# DRV8432.net
KiCad netlist of a schematic drawn in Altium Designer
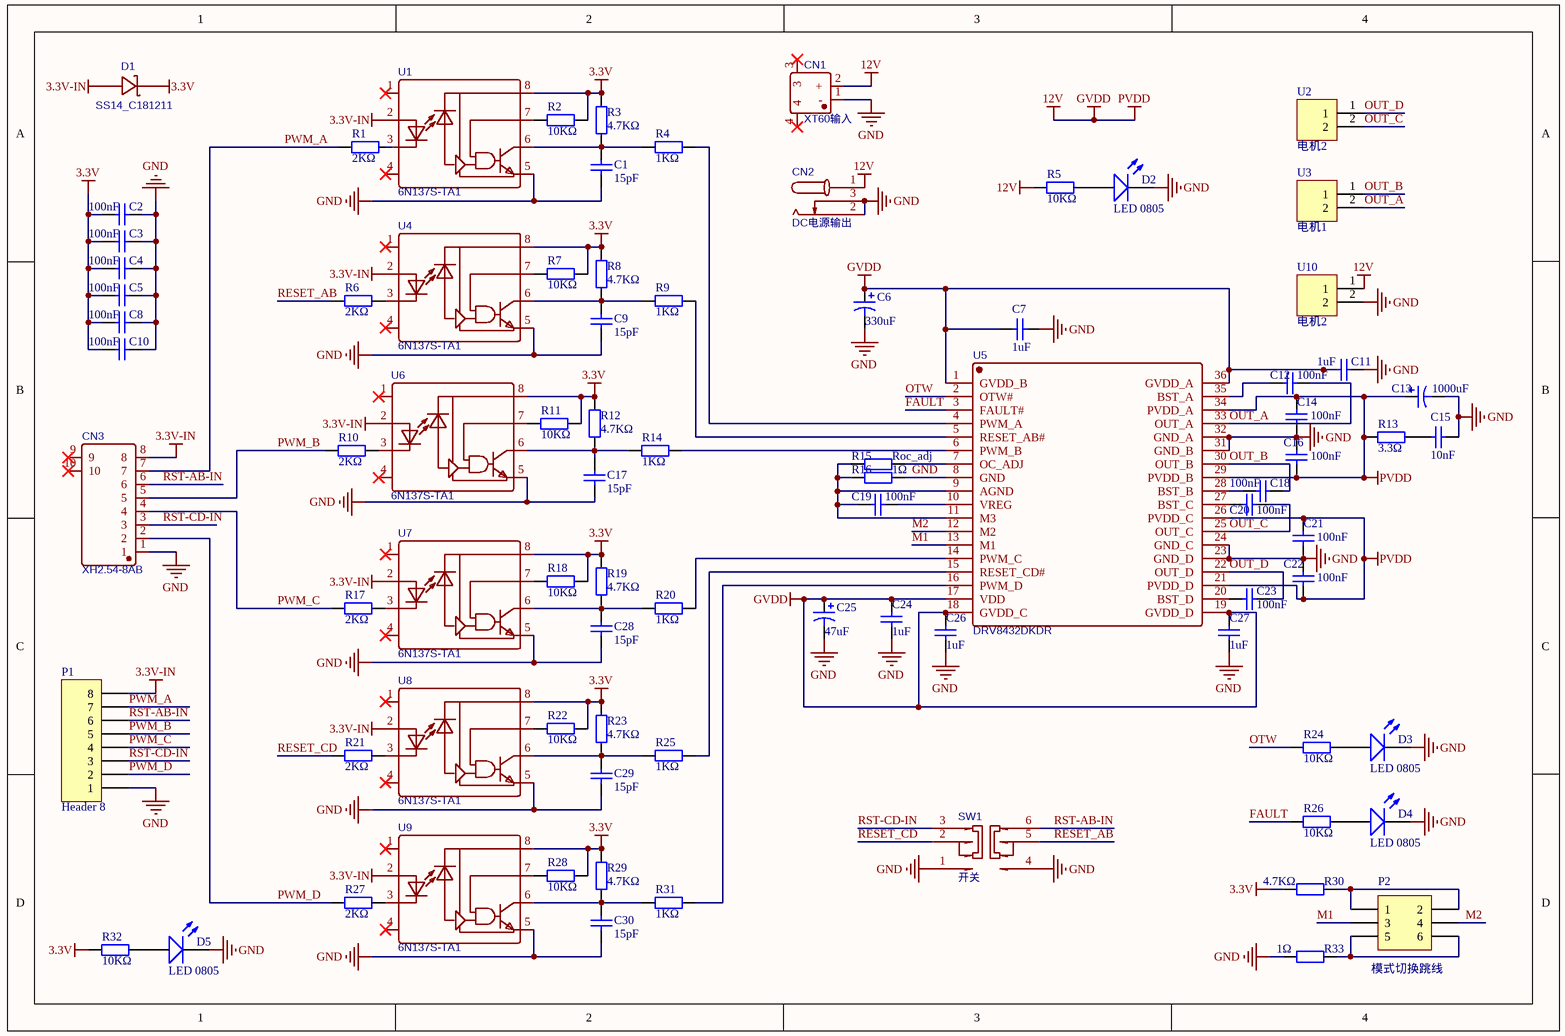
[diagram p0: DRV8432有刷直流电机驱动.SchDoc]

(export (version "E")
  (design (tool "Eeschema 10.0.6"))
  (components
    (comp (ref "C1")
      (value "15pF")
      (footprint "0805_C")
      (description "贴片电容")
      (libsource (lib "Miscellaneous Devices LC") (part "0805 15pF (150) 5% 50V"))
    )
    (comp (ref "C2")
      (value "100nF")
      (footprint "0805_C")
      (description "贴片电容")
      (libsource (lib "Miscellaneous Devices LC") (part "0805 100nF(104) 10% 50V"))
    )
    (comp (ref "C3")
      (value "100nF")
      (footprint "0805_C")
      (description "贴片电容")
      (libsource (lib "Miscellaneous Devices LC") (part "0805 100nF(104) 10% 50V"))
    )
    (comp (ref "C4")
      (value "100nF")
      (footprint "0805_C")
      (description "贴片电容")
      (libsource (lib "Miscellaneous Devices LC") (part "0805 100nF(104) 10% 50V"))
    )
    (comp (ref "C5")
      (value "100nF")
      (footprint "0805_C")
      (description "贴片电容")
      (libsource (lib "Miscellaneous Devices LC") (part "0805 100nF(104) 10% 50V"))
    )
    (comp (ref "C6")
      (value "330uF")
      (footprint "CAP-TH_BD8.0-P3.50-D0.6-FD")
      (description "Polarized Capacitor (Radial)")
      (fields (field (name "Comment") "Cap Pol1") (field (name "PUBLISHER") "Altium Limited"))
      (libsource (lib "Miscellaneous Devices") (part "Cap Pol1"))
    )
    (comp (ref "C7")
      (value "1uF")
      (footprint "0805_C")
      (description "贴片电容")
      (libsource (lib "Miscellaneous Devices LC") (part "0805 1uF (105) 10% 50V"))
    )
    (comp (ref "C8")
      (value "100nF")
      (footprint "0805_C")
      (description "贴片电容")
      (libsource (lib "Miscellaneous Devices LC") (part "0805 100nF(104) 10% 50V"))
    )
    (comp (ref "C9")
      (value "15pF")
      (footprint "0805_C")
      (description "贴片电容")
      (libsource (lib "Miscellaneous Devices LC") (part "0805 15pF (150) 5% 50V"))
    )
    (comp (ref "C10")
      (value "100nF")
      (footprint "0805_C")
      (description "贴片电容")
      (libsource (lib "Miscellaneous Devices LC") (part "0805 100nF(104) 10% 50V"))
    )
    (comp (ref "C11")
      (value "1uF")
      (footprint "0805_C")
      (description "贴片电容")
      (libsource (lib "Miscellaneous Devices LC") (part "0805 1uF (105) 10% 50V"))
    )
    (comp (ref "C12")
      (value "100nF")
      (footprint "0805_C")
      (description "贴片电容")
      (libsource (lib "Miscellaneous Devices LC") (part "0805 100nF(104) 10% 50V"))
    )
    (comp (ref "C13")
      (value "1000uF")
      (footprint "CAP-TH_BD25.0-P10.00-D2.3-FD")
      (description "Polarized Capacitor (Radial)")
      (fields (field (name "Comment") "Cap Pol1") (field (name "PUBLISHER") "Altium Limited"))
      (libsource (lib "Miscellaneous Devices") (part "Cap Pol1"))
    )
    (comp (ref "C14")
      (value "100nF")
      (footprint "0805_C")
      (description "贴片电容")
      (libsource (lib "Miscellaneous Devices LC") (part "0805 100nF(104) 10% 50V"))
    )
    (comp (ref "C15")
      (value "10nF")
      (footprint "0805_C")
      (description "贴片电容")
      (libsource (lib "Miscellaneous Devices LC") (part "0805 10nF (103) 10% 50V"))
    )
    (comp (ref "C16")
      (value "100nF")
      (footprint "0805_C")
      (description "贴片电容")
      (libsource (lib "Miscellaneous Devices LC") (part "0805 100nF(104) 10% 50V"))
    )
    (comp (ref "C17")
      (value "15pF")
      (footprint "0805_C")
      (description "贴片电容")
      (libsource (lib "Miscellaneous Devices LC") (part "0805 15pF (150) 5% 50V"))
    )
    (comp (ref "C18")
      (value "100nF")
      (footprint "0805_C")
      (description "贴片电容")
      (libsource (lib "Miscellaneous Devices LC") (part "0805 100nF(104) 10% 50V"))
    )
    (comp (ref "C19")
      (value "100nF")
      (footprint "0805_C")
      (description "贴片电容")
      (libsource (lib "Miscellaneous Devices LC") (part "0805 100nF(104) 10% 50V"))
    )
    (comp (ref "C20")
      (value "100nF")
      (footprint "0805_C")
      (description "贴片电容")
      (libsource (lib "Miscellaneous Devices LC") (part "0805 100nF(104) 10% 50V"))
    )
    (comp (ref "C21")
      (value "100nF")
      (footprint "0805_C")
      (description "贴片电容")
      (libsource (lib "Miscellaneous Devices LC") (part "0805 100nF(104) 10% 50V"))
    )
    (comp (ref "C22")
      (value "100nF")
      (footprint "0805_C")
      (description "贴片电容")
      (libsource (lib "Miscellaneous Devices LC") (part "0805 100nF(104) 10% 50V"))
    )
    (comp (ref "C23")
      (value "100nF")
      (footprint "0805_C")
      (description "贴片电容")
      (libsource (lib "Miscellaneous Devices LC") (part "0805 100nF(104) 10% 50V"))
    )
    (comp (ref "C24")
      (value "1uF")
      (footprint "0805_C")
      (description "贴片电容")
      (libsource (lib "Miscellaneous Devices LC") (part "0805 1uF (105) 10% 50V"))
    )
    (comp (ref "C25")
      (value "47uF")
      (footprint "CAP-TH_BD5.0-P2.00-D0.8-FD")
      (description "Polarized Capacitor (Radial)")
      (fields (field (name "Comment") "Cap Pol1") (field (name "PUBLISHER") "Altium Limited"))
      (libsource (lib "Miscellaneous Devices") (part "Cap Pol1"))
    )
    (comp (ref "C26")
      (value "1uF")
      (footprint "0805_C")
      (description "贴片电容")
      (libsource (lib "Miscellaneous Devices LC") (part "0805 1uF (105) 10% 50V"))
    )
    (comp (ref "C27")
      (value "1uF")
      (footprint "0805_C")
      (description "贴片电容")
      (libsource (lib "Miscellaneous Devices LC") (part "0805 1uF (105) 10% 50V"))
    )
    (comp (ref "C28")
      (value "15pF")
      (footprint "0805_C")
      (description "贴片电容")
      (libsource (lib "Miscellaneous Devices LC") (part "0805 15pF (150) 5% 50V"))
    )
    (comp (ref "C29")
      (value "15pF")
      (footprint "0805_C")
      (description "贴片电容")
      (libsource (lib "Miscellaneous Devices LC") (part "0805 15pF (150) 5% 50V"))
    )
    (comp (ref "C30")
      (value "15pF")
      (footprint "0805_C")
      (description "贴片电容")
      (libsource (lib "Miscellaneous Devices LC") (part "0805 15pF (150) 5% 50V"))
    )
    (comp (ref "CN1")
      (value "XT60输入")
      (footprint "XT60座子")
      (fields
        (field (name "BOM_SUPPLIER PART") "C98732")
        (field (name "BOM_MANUFACTURER PART") "XT60PW-M")
        (field (name "CONTRIBUTOR") "LCSC")
      )
      (libsource (lib "2021全地形") (part "XT60"))
    )
    (comp (ref "CN2")
      (value "DC电源输出")
      (footprint "DC接口5.5*2.1")
      (fields
        (field (name "BOM_MANUFACTURER PART") "DC-005-20A")
        (field (name "BOM_SUPPLIER PART") "C136744")
        (field (name "CONTRIBUTOR") "LCSC")
      )
      (libsource (lib "2021全地形") (part "DC接口2251"))
    )
    (comp (ref "CN3")
      (value "XH2.54-8AB")
      (footprint "CONN-SMD_8P-P2.54_XH2.54-8AB")
      (fields (field (name "BOM_SUPPLIER PART") "C146131") (field (name "CONTRIBUTOR") "LCSC"))
      (libsource (lib "2021全地形") (part "XH2.54-8AB"))
    )
    (comp (ref "D1")
      (value "SS14_C181211")
      (footprint "SMA_L4.4-W2.8-LS5.4-RD")
      (fields
        (field (name "BOM_MANUFACTURER PART") "SS14")
        (field (name "BOM_SUPPLIER PART") "C181211")
        (field (name "CONTRIBUTOR") "LCSC")
      )
      (libsource (lib "2021全地形") (part "SS14_C181211"))
    )
    (comp (ref "D2")
      (value "LED 0805")
      (footprint "0805_LED_S1")
      (description "发光二极管")
      (libsource (lib "Miscellaneous Devices LC") (part "0805 白灯"))
    )
    (comp (ref "D3")
      (value "LED 0805")
      (footprint "0805_LED_S1")
      (description "发光二极管")
      (libsource (lib "Miscellaneous Devices LC") (part "0805 白灯"))
    )
    (comp (ref "D4")
      (value "LED 0805")
      (footprint "0805_LED_S1")
      (description "发光二极管")
      (libsource (lib "Miscellaneous Devices LC") (part "0805 白灯"))
    )
    (comp (ref "D5")
      (value "LED 0805")
      (footprint "0805_LED_S1")
      (description "发光二极管")
      (libsource (lib "Miscellaneous Devices LC") (part "0805 白灯"))
    )
    (comp (ref "P1")
      (value "Header 8")
      (footprint "HDR1X8")
      (description "Header, 8-Pin")
      (fields (field (name "PUBLISHER") "Altium Limited"))
      (libsource (lib "Miscellaneous Connectors") (part "Header 8"))
    )
    (comp (ref "P2")
      (value "模式切换跳线")
      (footprint "HDR2X3")
      (description "Header, 3-Pin, Dual row")
      (fields (field (name "PUBLISHER") "Altium Limited"))
      (libsource (lib "Miscellaneous Connectors") (part "Header 3X2"))
    )
    (comp (ref "R1")
      (value "2KΩ")
      (footprint "0805_R")
      (description "贴片电阻")
      (libsource (lib "Miscellaneous Devices LC") (part "0805 2KΩ (2001) 1%"))
    )
    (comp (ref "R2")
      (value "10KΩ")
      (footprint "0805_R")
      (description "贴片电阻")
      (libsource (lib "Miscellaneous Devices LC") (part "0805 10KΩ (1002) 1%"))
    )
    (comp (ref "R3")
      (value "4.7KΩ")
      (footprint "0805_R")
      (description "贴片电阻")
      (libsource (lib "Miscellaneous Devices LC") (part "0805 4.7KΩ (4701) 1%"))
    )
    (comp (ref "R4")
      (value "1KΩ")
      (footprint "0805_R")
      (description "贴片电阻")
      (libsource (lib "Miscellaneous Devices LC") (part "0805 1KΩ (1001) 1%"))
    )
    (comp (ref "R5")
      (value "10KΩ")
      (footprint "0805_R")
      (description "贴片电阻")
      (libsource (lib "Miscellaneous Devices LC") (part "0805 10KΩ (1002) 1%"))
    )
    (comp (ref "R6")
      (value "2KΩ")
      (footprint "0805_R")
      (description "贴片电阻")
      (libsource (lib "Miscellaneous Devices LC") (part "0805 2KΩ (2001) 1%"))
    )
    (comp (ref "R7")
      (value "10KΩ")
      (footprint "0805_R")
      (description "贴片电阻")
      (libsource (lib "Miscellaneous Devices LC") (part "0805 10KΩ (1002) 1%"))
    )
    (comp (ref "R8")
      (value "4.7KΩ")
      (footprint "0805_R")
      (description "贴片电阻")
      (libsource (lib "Miscellaneous Devices LC") (part "0805 4.7KΩ (4701) 1%"))
    )
    (comp (ref "R9")
      (value "1KΩ")
      (footprint "0805_R")
      (description "贴片电阻")
      (libsource (lib "Miscellaneous Devices LC") (part "0805 1KΩ (1001) 1%"))
    )
    (comp (ref "R10")
      (value "2KΩ")
      (footprint "0805_R")
      (description "贴片电阻")
      (libsource (lib "Miscellaneous Devices LC") (part "0805 2KΩ (2001) 1%"))
    )
    (comp (ref "R11")
      (value "10KΩ")
      (footprint "0805_R")
      (description "贴片电阻")
      (libsource (lib "Miscellaneous Devices LC") (part "0805 10KΩ (1002) 1%"))
    )
    (comp (ref "R12")
      (value "4.7KΩ")
      (footprint "0805_R")
      (description "贴片电阻")
      (libsource (lib "Miscellaneous Devices LC") (part "0805 4.7KΩ (4701) 1%"))
    )
    (comp (ref "R13")
      (value "3.3Ω")
      (footprint "0805_R")
      (description "贴片电阻")
      (libsource (lib "Miscellaneous Devices LC") (part "0805 3.3KΩ (3301) 1%"))
    )
    (comp (ref "R14")
      (value "1KΩ")
      (footprint "0805_R")
      (description "贴片电阻")
      (libsource (lib "Miscellaneous Devices LC") (part "0805 1KΩ (1001) 1%"))
    )
    (comp (ref "R15")
      (value "Roc_adj")
      (footprint "0805_R")
      (description "贴片电阻")
      (libsource (lib "Miscellaneous Devices LC") (part "0805 1Ω (1R00) 1%"))
    )
    (comp (ref "R16")
      (value "1Ω")
      (footprint "0805_R")
      (description "贴片电阻")
      (libsource (lib "Miscellaneous Devices LC") (part "0805 1Ω (1R00) 1%"))
    )
    (comp (ref "R17")
      (value "2KΩ")
      (footprint "0805_R")
      (description "贴片电阻")
      (libsource (lib "Miscellaneous Devices LC") (part "0805 2KΩ (2001) 1%"))
    )
    (comp (ref "R18")
      (value "10KΩ")
      (footprint "0805_R")
      (description "贴片电阻")
      (libsource (lib "Miscellaneous Devices LC") (part "0805 10KΩ (1002) 1%"))
    )
    (comp (ref "R19")
      (value "4.7KΩ")
      (footprint "0805_R")
      (description "贴片电阻")
      (libsource (lib "Miscellaneous Devices LC") (part "0805 4.7KΩ (4701) 1%"))
    )
    (comp (ref "R20")
      (value "1KΩ")
      (footprint "0805_R")
      (description "贴片电阻")
      (libsource (lib "Miscellaneous Devices LC") (part "0805 1KΩ (1001) 1%"))
    )
    (comp (ref "R21")
      (value "2KΩ")
      (footprint "0805_R")
      (description "贴片电阻")
      (libsource (lib "Miscellaneous Devices LC") (part "0805 2KΩ (2001) 1%"))
    )
    (comp (ref "R22")
      (value "10KΩ")
      (footprint "0805_R")
      (description "贴片电阻")
      (libsource (lib "Miscellaneous Devices LC") (part "0805 10KΩ (1002) 1%"))
    )
    (comp (ref "R23")
      (value "4.7KΩ")
      (footprint "0805_R")
      (description "贴片电阻")
      (libsource (lib "Miscellaneous Devices LC") (part "0805 4.7KΩ (4701) 1%"))
    )
    (comp (ref "R24")
      (value "10KΩ")
      (footprint "0805_R")
      (description "贴片电阻")
      (libsource (lib "Miscellaneous Devices LC") (part "0805 10KΩ (1002) 1%"))
    )
    (comp (ref "R25")
      (value "1KΩ")
      (footprint "0805_R")
      (description "贴片电阻")
      (libsource (lib "Miscellaneous Devices LC") (part "0805 1KΩ (1001) 1%"))
    )
    (comp (ref "R26")
      (value "10KΩ")
      (footprint "0805_R")
      (description "贴片电阻")
      (libsource (lib "Miscellaneous Devices LC") (part "0805 10KΩ (1002) 1%"))
    )
    (comp (ref "R27")
      (value "2KΩ")
      (footprint "0805_R")
      (description "贴片电阻")
      (libsource (lib "Miscellaneous Devices LC") (part "0805 2KΩ (2001) 1%"))
    )
    (comp (ref "R28")
      (value "10KΩ")
      (footprint "0805_R")
      (description "贴片电阻")
      (libsource (lib "Miscellaneous Devices LC") (part "0805 10KΩ (1002) 1%"))
    )
    (comp (ref "R29")
      (value "4.7KΩ")
      (footprint "0805_R")
      (description "贴片电阻")
      (libsource (lib "Miscellaneous Devices LC") (part "0805 4.7KΩ (4701) 1%"))
    )
    (comp (ref "R30")
      (value "4.7KΩ")
      (footprint "0805_R")
      (description "贴片电阻")
      (libsource (lib "") (part "0805 4.7KΩ (4701) 1%_1"))
    )
    (comp (ref "R31")
      (value "1KΩ")
      (footprint "0805_R")
      (description "贴片电阻")
      (libsource (lib "Miscellaneous Devices LC") (part "0805 1KΩ (1001) 1%"))
    )
    (comp (ref "R32")
      (value "10KΩ")
      (footprint "0805_R")
      (description "贴片电阻")
      (libsource (lib "Miscellaneous Devices LC") (part "0805 10KΩ (1002) 1%"))
    )
    (comp (ref "R33")
      (value "1Ω")
      (footprint "0805_R")
      (description "贴片电阻")
      (libsource (lib "Miscellaneous Devices LC") (part "0805 1Ω (1R00) 1%"))
    )
    (comp (ref "SW1")
      (value "开关")
      (footprint "贴片6P拨动开关")
      (fields
        (field (name "BOM_SUPPLIER PART") "C381098")
        (field (name "BOM_MANUFACTURER PART") "SS-3235S-L3")
        (field (name "CONTRIBUTOR") "LCSC")
      )
      (libsource (lib "2021全地形") (part "6P拨动开关"))
    )
    (comp (ref "U1")
      (value "6N137S-TA1")
      (footprint "SOP-8_L9.8-W6.6-P2.54-LS10.3-BL")
      (fields (field (name "BOM_SUPPLIER PART") "C92651"))
      (libsource (lib "2021全地形") (part "6N137S-TA1"))
    )
    (comp (ref "U2") (value "电机2") (footprint "2Pin大接线端子") (libsource (lib "2021全地形") (part "接线端子")))
    (comp (ref "U3") (value "电机1") (footprint "2Pin大接线端子") (libsource (lib "2021全地形") (part "接线端子")))
    (comp (ref "U4")
      (value "6N137S-TA1")
      (footprint "SOP-8_L9.8-W6.6-P2.54-LS10.3-BL")
      (fields (field (name "BOM_SUPPLIER PART") "C92651"))
      (libsource (lib "2021全地形") (part "6N137S-TA1"))
    )
    (comp (ref "U5")
      (value "DRV8432DKDR")
      (footprint "HSSOP-36_L16.0-W11.0-P0.65-LS14.2-BL")
      (fields (field (name "BOM_SUPPLIER PART") "C79853"))
      (libsource (lib "2021全地形") (part "DRV8432DKDR"))
    )
    (comp (ref "U6")
      (value "6N137S-TA1")
      (footprint "SOP-8_L9.8-W6.6-P2.54-LS10.3-BL")
      (fields (field (name "BOM_SUPPLIER PART") "C92651"))
      (libsource (lib "2021全地形") (part "6N137S-TA1"))
    )
    (comp (ref "U7")
      (value "6N137S-TA1")
      (footprint "SOP-8_L9.8-W6.6-P2.54-LS10.3-BL")
      (fields (field (name "BOM_SUPPLIER PART") "C92651"))
      (libsource (lib "2021全地形") (part "6N137S-TA1"))
    )
    (comp (ref "U8")
      (value "6N137S-TA1")
      (footprint "SOP-8_L9.8-W6.6-P2.54-LS10.3-BL")
      (fields (field (name "BOM_SUPPLIER PART") "C92651"))
      (libsource (lib "2021全地形") (part "6N137S-TA1"))
    )
    (comp (ref "U9")
      (value "6N137S-TA1")
      (footprint "SOP-8_L9.8-W6.6-P2.54-LS10.3-BL")
      (fields (field (name "BOM_SUPPLIER PART") "C92651"))
      (libsource (lib "2021全地形") (part "6N137S-TA1"))
    )
    (comp (ref "U10") (value "电机2") (footprint "2Pin大接线端子") (libsource (lib "2021全地形") (part "接线端子")))
  )
  (nets
    (net (code "1") (name "/FAULT") (class "Default")
      (node (ref "R26") (pin "1") (pinfunction "1_1") (pintype "passive"))
      (node (ref "U5") (pin "3") (pinfunction "FAULT#_3") (pintype "passive"))
    )
    (net (code "2") (name "/M1") (class "Default")
      (node (ref "P2") (pin "3") (pinfunction "3_3") (pintype "passive"))
      (node (ref "U5") (pin "13") (pinfunction "M1_13") (pintype "passive"))
    )
    (net (code "3") (name "/M2") (class "Default")
      (node (ref "P2") (pin "4") (pinfunction "4_4") (pintype "passive"))
      (node (ref "U5") (pin "12") (pinfunction "M2_12") (pintype "passive"))
    )
    (net (code "4") (name "/OTW") (class "Default")
      (node (ref "R24") (pin "1") (pinfunction "1_1") (pintype "passive"))
      (node (ref "U5") (pin "2") (pinfunction "OTW#_2") (pintype "passive"))
    )
    (net (code "5") (name "/OUT_A") (class "Default")
      (node (ref "C12") (pin "2") (pinfunction "2_2") (pintype "passive"))
      (node (ref "U3") (pin "2") (pinfunction "2_2") (pintype "passive"))
      (node (ref "U5") (pin "33") (pinfunction "OUT_A_33") (pintype "passive"))
    )
    (net (code "6") (name "/OUT_B") (class "Default")
      (node (ref "C18") (pin "2") (pinfunction "2_2") (pintype "passive"))
      (node (ref "U3") (pin "1") (pinfunction "1_1") (pintype "passive"))
      (node (ref "U5") (pin "30") (pinfunction "OUT_B_30") (pintype "passive"))
    )
    (net (code "7") (name "/OUT_C") (class "Default")
      (node (ref "C20") (pin "2") (pinfunction "2_2") (pintype "passive"))
      (node (ref "U2") (pin "2") (pinfunction "2_2") (pintype "passive"))
      (node (ref "U5") (pin "25") (pinfunction "OUT_C_25") (pintype "passive"))
    )
    (net (code "8") (name "/OUT_D") (class "Default")
      (node (ref "C23") (pin "1") (pinfunction "1_1") (pintype "passive"))
      (node (ref "U2") (pin "1") (pinfunction "1_1") (pintype "passive"))
      (node (ref "U5") (pin "22") (pinfunction "OUT_D_22") (pintype "passive"))
    )
    (net (code "9") (name "/PWM_A") (class "Default")
      (node (ref "CN3") (pin "7") (pinfunction "7_7") (pintype "passive"))
      (node (ref "P1") (pin "7") (pinfunction "7_7") (pintype "passive"))
      (node (ref "R1") (pin "1") (pinfunction "1_1") (pintype "passive"))
    )
    (net (code "10") (name "/PWM_B") (class "Default")
      (node (ref "CN3") (pin "5") (pinfunction "5_5") (pintype "passive"))
      (node (ref "P1") (pin "5") (pinfunction "5_5") (pintype "passive"))
      (node (ref "R10") (pin "1") (pinfunction "1_1") (pintype "passive"))
    )
    (net (code "11") (name "/PWM_C") (class "Default")
      (node (ref "CN3") (pin "4") (pinfunction "4_4") (pintype "passive"))
      (node (ref "P1") (pin "4") (pinfunction "4_4") (pintype "passive"))
      (node (ref "R17") (pin "1") (pinfunction "1_1") (pintype "passive"))
    )
    (net (code "12") (name "/PWM_D") (class "Default")
      (node (ref "CN3") (pin "2") (pinfunction "2_2") (pintype "passive"))
      (node (ref "P1") (pin "2") (pinfunction "2_2") (pintype "passive"))
      (node (ref "R27") (pin "1") (pinfunction "1_1") (pintype "passive"))
    )
    (net (code "13") (name "/RESET_AB") (class "Default")
      (node (ref "R6") (pin "1") (pinfunction "1_1") (pintype "passive"))
      (node (ref "SW1") (pin "5") (pinfunction "5_5") (pintype "passive"))
    )
    (net (code "14") (name "/RESET_CD") (class "Default")
      (node (ref "R21") (pin "1") (pinfunction "1_1") (pintype "passive"))
      (node (ref "SW1") (pin "2") (pinfunction "2_2") (pintype "passive"))
    )
    (net (code "15") (name "/RST-AB-IN") (class "Default")
      (node (ref "CN3") (pin "6") (pinfunction "6_6") (pintype "passive"))
      (node (ref "P1") (pin "6") (pinfunction "6_6") (pintype "passive"))
      (node (ref "SW1") (pin "6") (pinfunction "6_6") (pintype "passive"))
    )
    (net (code "16") (name "/RST-CD-IN") (class "Default")
      (node (ref "CN3") (pin "3") (pinfunction "3_3") (pintype "passive"))
      (node (ref "P1") (pin "3") (pinfunction "3_3") (pintype "passive"))
      (node (ref "SW1") (pin "3") (pinfunction "3_3") (pintype "passive"))
    )
    (net (code "17") (name "3.3V") (class "Default")
      (node (ref "C10") (pin "2") (pinfunction "2_2") (pintype "passive"))
      (node (ref "C2") (pin "2") (pinfunction "2_2") (pintype "passive"))
      (node (ref "C3") (pin "2") (pinfunction "2_2") (pintype "passive"))
      (node (ref "C4") (pin "2") (pinfunction "2_2") (pintype "passive"))
      (node (ref "C5") (pin "2") (pinfunction "2_2") (pintype "passive"))
      (node (ref "C8") (pin "2") (pinfunction "2_2") (pintype "passive"))
      (node (ref "D1") (pin "1") (pinfunction "K_1") (pintype "passive"))
      (node (ref "R11") (pin "2") (pinfunction "2_2") (pintype "passive"))
      (node (ref "R12") (pin "2") (pinfunction "2_2") (pintype "passive"))
      (node (ref "R18") (pin "2") (pinfunction "2_2") (pintype "passive"))
      (node (ref "R19") (pin "2") (pinfunction "2_2") (pintype "passive"))
      (node (ref "R2") (pin "2") (pinfunction "2_2") (pintype "passive"))
      (node (ref "R22") (pin "2") (pinfunction "2_2") (pintype "passive"))
      (node (ref "R23") (pin "2") (pinfunction "2_2") (pintype "passive"))
      (node (ref "R28") (pin "2") (pinfunction "2_2") (pintype "passive"))
      (node (ref "R29") (pin "2") (pinfunction "2_2") (pintype "passive"))
      (node (ref "R3") (pin "2") (pinfunction "2_2") (pintype "passive"))
      (node (ref "R30") (pin "2") (pinfunction "2_2") (pintype "passive"))
      (node (ref "R32") (pin "1") (pinfunction "1_1") (pintype "passive"))
      (node (ref "R7") (pin "2") (pinfunction "2_2") (pintype "passive"))
      (node (ref "R8") (pin "2") (pinfunction "2_2") (pintype "passive"))
      (node (ref "U1") (pin "8") (pinfunction "8_8") (pintype "passive"))
      (node (ref "U4") (pin "8") (pinfunction "8_8") (pintype "passive"))
      (node (ref "U6") (pin "8") (pinfunction "8_8") (pintype "passive"))
      (node (ref "U7") (pin "8") (pinfunction "8_8") (pintype "passive"))
      (node (ref "U8") (pin "8") (pinfunction "8_8") (pintype "passive"))
      (node (ref "U9") (pin "8") (pinfunction "8_8") (pintype "passive"))
    )
    (net (code "18") (name "3.3V-IN") (class "Default")
      (node (ref "CN3") (pin "8") (pinfunction "8_8") (pintype "passive"))
      (node (ref "D1") (pin "2") (pinfunction "A_2") (pintype "passive"))
      (node (ref "P1") (pin "8") (pinfunction "8_8") (pintype "passive"))
      (node (ref "U1") (pin "2") (pinfunction "2_2") (pintype "passive"))
      (node (ref "U4") (pin "2") (pinfunction "2_2") (pintype "passive"))
      (node (ref "U6") (pin "2") (pinfunction "2_2") (pintype "passive"))
      (node (ref "U7") (pin "2") (pinfunction "2_2") (pintype "passive"))
      (node (ref "U8") (pin "2") (pinfunction "2_2") (pintype "passive"))
      (node (ref "U9") (pin "2") (pinfunction "2_2") (pintype "passive"))
    )
    (net (code "19") (name "12V") (class "Default")
      (node (ref "C11") (pin "2") (pinfunction "2_2") (pintype "passive"))
      (node (ref "C13") (pin "1") (pinfunction "1_1") (pintype "passive"))
      (node (ref "C14") (pin "2") (pinfunction "2_2") (pintype "passive"))
      (node (ref "C16") (pin "1") (pinfunction "1_1") (pintype "passive"))
      (node (ref "C21") (pin "2") (pinfunction "2_2") (pintype "passive"))
      (node (ref "C22") (pin "1") (pinfunction "1_1") (pintype "passive"))
      (node (ref "C24") (pin "2") (pinfunction "2_2") (pintype "passive"))
      (node (ref "C25") (pin "1") (pinfunction "1_1") (pintype "passive"))
      (node (ref "C26") (pin "2") (pinfunction "2_2") (pintype "passive"))
      (node (ref "C27") (pin "2") (pinfunction "2_2") (pintype "passive"))
      (node (ref "C6") (pin "1") (pinfunction "1_1") (pintype "passive"))
      (node (ref "C7") (pin "1") (pinfunction "1_1") (pintype "passive"))
      (node (ref "CN1") (pin "2") (pinfunction "+_2") (pintype "passive"))
      (node (ref "CN2") (pin "1") (pinfunction "1_1") (pintype "passive"))
      (node (ref "R13") (pin "1") (pinfunction "1_1") (pintype "passive"))
      (node (ref "R5") (pin "1") (pinfunction "1_1") (pintype "passive"))
      (node (ref "U10") (pin "1") (pinfunction "1_1") (pintype "passive"))
      (node (ref "U5") (pin "1") (pinfunction "GVDD_B_1") (pintype "passive"))
      (node (ref "U5") (pin "17") (pinfunction "VDD_17") (pintype "passive"))
      (node (ref "U5") (pin "18") (pinfunction "GVDD_C_18") (pintype "passive"))
      (node (ref "U5") (pin "19") (pinfunction "GVDD_D_19") (pintype "passive"))
      (node (ref "U5") (pin "21") (pinfunction "PVDD_D_21") (pintype "passive"))
      (node (ref "U5") (pin "26") (pinfunction "PVDD_C_26") (pintype "passive"))
      (node (ref "U5") (pin "29") (pinfunction "PVDD_B_29") (pintype "passive"))
      (node (ref "U5") (pin "34") (pinfunction "PVDD_A_34") (pintype "passive"))
      (node (ref "U5") (pin "36") (pinfunction "GVDD_A_36") (pintype "passive"))
    )
    (net (code "20") (name "GND") (class "Default")
      (node (ref "C1") (pin "1") (pinfunction "1_1") (pintype "passive"))
      (node (ref "C10") (pin "1") (pinfunction "1_1") (pintype "passive"))
      (node (ref "C11") (pin "1") (pinfunction "1_1") (pintype "passive"))
      (node (ref "C13") (pin "2") (pinfunction "2_2") (pintype "passive"))
      (node (ref "C14") (pin "1") (pinfunction "1_1") (pintype "passive"))
      (node (ref "C15") (pin "2") (pinfunction "2_2") (pintype "passive"))
      (node (ref "C16") (pin "2") (pinfunction "2_2") (pintype "passive"))
      (node (ref "C17") (pin "1") (pinfunction "1_1") (pintype "passive"))
      (node (ref "C2") (pin "1") (pinfunction "1_1") (pintype "passive"))
      (node (ref "C21") (pin "1") (pinfunction "1_1") (pintype "passive"))
      (node (ref "C22") (pin "2") (pinfunction "2_2") (pintype "passive"))
      (node (ref "C24") (pin "1") (pinfunction "1_1") (pintype "passive"))
      (node (ref "C25") (pin "2") (pinfunction "2_2") (pintype "passive"))
      (node (ref "C26") (pin "1") (pinfunction "1_1") (pintype "passive"))
      (node (ref "C27") (pin "1") (pinfunction "1_1") (pintype "passive"))
      (node (ref "C28") (pin "1") (pinfunction "1_1") (pintype "passive"))
      (node (ref "C29") (pin "1") (pinfunction "1_1") (pintype "passive"))
      (node (ref "C3") (pin "1") (pinfunction "1_1") (pintype "passive"))
      (node (ref "C30") (pin "1") (pinfunction "1_1") (pintype "passive"))
      (node (ref "C4") (pin "1") (pinfunction "1_1") (pintype "passive"))
      (node (ref "C5") (pin "1") (pinfunction "1_1") (pintype "passive"))
      (node (ref "C6") (pin "2") (pinfunction "2_2") (pintype "passive"))
      (node (ref "C7") (pin "2") (pinfunction "2_2") (pintype "passive"))
      (node (ref "C8") (pin "1") (pinfunction "1_1") (pintype "passive"))
      (node (ref "C9") (pin "1") (pinfunction "1_1") (pintype "passive"))
      (node (ref "CN1") (pin "1") (pinfunction "-_1") (pintype "passive"))
      (node (ref "CN2") (pin "2") (pinfunction "2_2") (pintype "passive"))
      (node (ref "CN2") (pin "3") (pinfunction "3_3") (pintype "passive"))
      (node (ref "CN3") (pin "1") (pinfunction "1_1") (pintype "passive"))
      (node (ref "D2") (pin "K") (pinfunction "K_K") (pintype "passive"))
      (node (ref "D3") (pin "K") (pinfunction "K_K") (pintype "passive"))
      (node (ref "D4") (pin "K") (pinfunction "K_K") (pintype "passive"))
      (node (ref "D5") (pin "K") (pinfunction "K_K") (pintype "passive"))
      (node (ref "P1") (pin "1") (pinfunction "1_1") (pintype "passive"))
      (node (ref "R16") (pin "1") (pinfunction "1_1") (pintype "passive"))
      (node (ref "R33") (pin "2") (pinfunction "2_2") (pintype "passive"))
      (node (ref "SW1") (pin "1") (pinfunction "1_1") (pintype "passive"))
      (node (ref "SW1") (pin "4") (pinfunction "4_4") (pintype "passive"))
      (node (ref "U1") (pin "5") (pinfunction "5_5") (pintype "passive"))
      (node (ref "U10") (pin "2") (pinfunction "2_2") (pintype "passive"))
      (node (ref "U4") (pin "5") (pinfunction "5_5") (pintype "passive"))
      (node (ref "U5") (pin "23") (pinfunction "GND_D_23") (pintype "passive"))
      (node (ref "U5") (pin "24") (pinfunction "GND_C_24") (pintype "passive"))
      (node (ref "U5") (pin "31") (pinfunction "GND_B_31") (pintype "passive"))
      (node (ref "U5") (pin "32") (pinfunction "GND_A_32") (pintype "passive"))
      (node (ref "U5") (pin "8") (pinfunction "GND_8") (pintype "passive"))
      (node (ref "U6") (pin "5") (pinfunction "5_5") (pintype "passive"))
      (node (ref "U7") (pin "5") (pinfunction "5_5") (pintype "passive"))
      (node (ref "U8") (pin "5") (pinfunction "5_5") (pintype "passive"))
      (node (ref "U9") (pin "5") (pinfunction "5_5") (pintype "passive"))
    )
    (net (code "21") (name "Net-(C1-Pad2)") (class "Default")
      (node (ref "C1") (pin "2") (pinfunction "2_2") (pintype "passive"))
      (node (ref "R3") (pin "1") (pinfunction "1_1") (pintype "passive"))
      (node (ref "R4") (pin "1") (pinfunction "1_1") (pintype "passive"))
      (node (ref "U1") (pin "6") (pinfunction "6_6") (pintype "passive"))
    )
    (net (code "22") (name "Net-(C9-Pad2)") (class "Default")
      (node (ref "C9") (pin "2") (pinfunction "2_2") (pintype "passive"))
      (node (ref "R8") (pin "1") (pinfunction "1_1") (pintype "passive"))
      (node (ref "R9") (pin "1") (pinfunction "1_1") (pintype "passive"))
      (node (ref "U4") (pin "6") (pinfunction "6_6") (pintype "passive"))
    )
    (net (code "23") (name "Net-(C15-Pad1)") (class "Default")
      (node (ref "C15") (pin "1") (pinfunction "1_1") (pintype "passive"))
      (node (ref "R13") (pin "2") (pinfunction "2_2") (pintype "passive"))
    )
    (net (code "24") (name "Net-(C17-Pad2)") (class "Default")
      (node (ref "C17") (pin "2") (pinfunction "2_2") (pintype "passive"))
      (node (ref "R12") (pin "1") (pinfunction "1_1") (pintype "passive"))
      (node (ref "R14") (pin "1") (pinfunction "1_1") (pintype "passive"))
      (node (ref "U6") (pin "6") (pinfunction "6_6") (pintype "passive"))
    )
    (net (code "25") (name "Net-(C28-Pad2)") (class "Default")
      (node (ref "C28") (pin "2") (pinfunction "2_2") (pintype "passive"))
      (node (ref "R19") (pin "1") (pinfunction "1_1") (pintype "passive"))
      (node (ref "R20") (pin "1") (pinfunction "1_1") (pintype "passive"))
      (node (ref "U7") (pin "6") (pinfunction "6_6") (pintype "passive"))
    )
    (net (code "26") (name "Net-(C29-Pad2)") (class "Default")
      (node (ref "C29") (pin "2") (pinfunction "2_2") (pintype "passive"))
      (node (ref "R23") (pin "1") (pinfunction "1_1") (pintype "passive"))
      (node (ref "R25") (pin "1") (pinfunction "1_1") (pintype "passive"))
      (node (ref "U8") (pin "6") (pinfunction "6_6") (pintype "passive"))
    )
    (net (code "27") (name "Net-(C30-Pad2)") (class "Default")
      (node (ref "C30") (pin "2") (pinfunction "2_2") (pintype "passive"))
      (node (ref "R29") (pin "1") (pinfunction "1_1") (pintype "passive"))
      (node (ref "R31") (pin "1") (pinfunction "1_1") (pintype "passive"))
      (node (ref "U9") (pin "6") (pinfunction "6_6") (pintype "passive"))
    )
    (net (code "28") (name "Net-(D2-PadA)") (class "Default")
      (node (ref "D2") (pin "A") (pinfunction "A_A") (pintype "passive"))
      (node (ref "R5") (pin "2") (pinfunction "2_2") (pintype "passive"))
    )
    (net (code "29") (name "Net-(D3-PadA)") (class "Default")
      (node (ref "D3") (pin "A") (pinfunction "A_A") (pintype "passive"))
      (node (ref "R24") (pin "2") (pinfunction "2_2") (pintype "passive"))
    )
    (net (code "30") (name "Net-(D4-PadA)") (class "Default")
      (node (ref "D4") (pin "A") (pinfunction "A_A") (pintype "passive"))
      (node (ref "R26") (pin "2") (pinfunction "2_2") (pintype "passive"))
    )
    (net (code "31") (name "Net-(D5-PadA)") (class "Default")
      (node (ref "D5") (pin "A") (pinfunction "A_A") (pintype "passive"))
      (node (ref "R32") (pin "2") (pinfunction "2_2") (pintype "passive"))
    )
    (net (code "32") (name "Net-(P2-Pad1)") (class "Default")
      (node (ref "P2") (pin "1") (pinfunction "1_1") (pintype "passive"))
      (node (ref "P2") (pin "2") (pinfunction "2_2") (pintype "passive"))
      (node (ref "R30") (pin "1") (pinfunction "1_1") (pintype "passive"))
    )
    (net (code "33") (name "Net-(P2-Pad5)") (class "Default")
      (node (ref "P2") (pin "5") (pinfunction "5_5") (pintype "passive"))
      (node (ref "P2") (pin "6") (pinfunction "6_6") (pintype "passive"))
      (node (ref "R33") (pin "1") (pinfunction "1_1") (pintype "passive"))
    )
    (net (code "34") (name "Net-(R1-Pad2)") (class "Default")
      (node (ref "R1") (pin "2") (pinfunction "2_2") (pintype "passive"))
      (node (ref "U1") (pin "3") (pinfunction "3_3") (pintype "passive"))
    )
    (net (code "35") (name "Net-(R2-Pad1)") (class "Default")
      (node (ref "R2") (pin "1") (pinfunction "1_1") (pintype "passive"))
      (node (ref "U1") (pin "7") (pinfunction "7_7") (pintype "passive"))
    )
    (net (code "36") (name "Net-(R6-Pad2)") (class "Default")
      (node (ref "R6") (pin "2") (pinfunction "2_2") (pintype "passive"))
      (node (ref "U4") (pin "3") (pinfunction "3_3") (pintype "passive"))
    )
    (net (code "37") (name "Net-(R7-Pad1)") (class "Default")
      (node (ref "R7") (pin "1") (pinfunction "1_1") (pintype "passive"))
      (node (ref "U4") (pin "7") (pinfunction "7_7") (pintype "passive"))
    )
    (net (code "38") (name "Net-(R10-Pad2)") (class "Default")
      (node (ref "R10") (pin "2") (pinfunction "2_2") (pintype "passive"))
      (node (ref "U6") (pin "3") (pinfunction "3_3") (pintype "passive"))
    )
    (net (code "39") (name "Net-(R11-Pad1)") (class "Default")
      (node (ref "R11") (pin "1") (pinfunction "1_1") (pintype "passive"))
      (node (ref "U6") (pin "7") (pinfunction "7_7") (pintype "passive"))
    )
    (net (code "40") (name "Net-(R17-Pad2)") (class "Default")
      (node (ref "R17") (pin "2") (pinfunction "2_2") (pintype "passive"))
      (node (ref "U7") (pin "3") (pinfunction "3_3") (pintype "passive"))
    )
    (net (code "41") (name "Net-(R18-Pad1)") (class "Default")
      (node (ref "R18") (pin "1") (pinfunction "1_1") (pintype "passive"))
      (node (ref "U7") (pin "7") (pinfunction "7_7") (pintype "passive"))
    )
    (net (code "42") (name "Net-(R21-Pad2)") (class "Default")
      (node (ref "R21") (pin "2") (pinfunction "2_2") (pintype "passive"))
      (node (ref "U8") (pin "3") (pinfunction "3_3") (pintype "passive"))
    )
    (net (code "43") (name "Net-(R22-Pad1)") (class "Default")
      (node (ref "R22") (pin "1") (pinfunction "1_1") (pintype "passive"))
      (node (ref "U8") (pin "7") (pinfunction "7_7") (pintype "passive"))
    )
    (net (code "44") (name "Net-(R27-Pad2)") (class "Default")
      (node (ref "R27") (pin "2") (pinfunction "2_2") (pintype "passive"))
      (node (ref "U9") (pin "3") (pinfunction "3_3") (pintype "passive"))
    )
    (net (code "45") (name "Net-(R28-Pad1)") (class "Default")
      (node (ref "R28") (pin "1") (pinfunction "1_1") (pintype "passive"))
      (node (ref "U9") (pin "7") (pinfunction "7_7") (pintype "passive"))
    )
    (net (code "46") (name "Net-(U5-AGND)") (class "Default")
      (node (ref "C19") (pin "1") (pinfunction "1_1") (pintype "passive"))
      (node (ref "R15") (pin "2") (pinfunction "2_2") (pintype "passive"))
      (node (ref "R16") (pin "2") (pinfunction "2_2") (pintype "passive"))
      (node (ref "U5") (pin "11") (pinfunction "M3_11") (pintype "passive"))
      (node (ref "U5") (pin "9") (pinfunction "AGND_9") (pintype "passive"))
    )
    (net (code "47") (name "Net-(U5-BST_A)") (class "Default")
      (node (ref "C12") (pin "1") (pinfunction "1_1") (pintype "passive"))
      (node (ref "U5") (pin "35") (pinfunction "BST_A_35") (pintype "passive"))
    )
    (net (code "48") (name "Net-(U5-BST_B)") (class "Default")
      (node (ref "C18") (pin "1") (pinfunction "1_1") (pintype "passive"))
      (node (ref "U5") (pin "28") (pinfunction "BST_B_28") (pintype "passive"))
    )
    (net (code "49") (name "Net-(U5-BST_C)") (class "Default")
      (node (ref "C20") (pin "1") (pinfunction "1_1") (pintype "passive"))
      (node (ref "U5") (pin "27") (pinfunction "BST_C_27") (pintype "passive"))
    )
    (net (code "50") (name "Net-(U5-BST_D)") (class "Default")
      (node (ref "C23") (pin "2") (pinfunction "2_2") (pintype "passive"))
      (node (ref "U5") (pin "20") (pinfunction "BST_D_20") (pintype "passive"))
    )
    (net (code "51") (name "Net-(U5-OC_ADJ)") (class "Default")
      (node (ref "R15") (pin "1") (pinfunction "1_1") (pintype "passive"))
      (node (ref "U5") (pin "7") (pinfunction "OC_ADJ_7") (pintype "passive"))
    )
    (net (code "52") (name "Net-(U5-PWM_A)") (class "Default")
      (node (ref "R4") (pin "2") (pinfunction "2_2") (pintype "passive"))
      (node (ref "U5") (pin "4") (pinfunction "PWM_A_4") (pintype "passive"))
    )
    (net (code "53") (name "Net-(U5-PWM_B)") (class "Default")
      (node (ref "R14") (pin "2") (pinfunction "2_2") (pintype "passive"))
      (node (ref "U5") (pin "6") (pinfunction "PWM_B_6") (pintype "passive"))
    )
    (net (code "54") (name "Net-(U5-PWM_C)") (class "Default")
      (node (ref "R20") (pin "2") (pinfunction "2_2") (pintype "passive"))
      (node (ref "U5") (pin "14") (pinfunction "PWM_C_14") (pintype "passive"))
    )
    (net (code "55") (name "Net-(U5-PWM_D)") (class "Default")
      (node (ref "R31") (pin "2") (pinfunction "2_2") (pintype "passive"))
      (node (ref "U5") (pin "16") (pinfunction "PWM_D_16") (pintype "passive"))
    )
    (net (code "56") (name "Net-(U5-RESET_AB#)") (class "Default")
      (node (ref "R9") (pin "2") (pinfunction "2_2") (pintype "passive"))
      (node (ref "U5") (pin "5") (pinfunction "RESET_AB#_5") (pintype "passive"))
    )
    (net (code "57") (name "Net-(U5-RESET_CD#)") (class "Default")
      (node (ref "R25") (pin "2") (pinfunction "2_2") (pintype "passive"))
      (node (ref "U5") (pin "15") (pinfunction "RESET_CD#_15") (pintype "passive"))
    )
    (net (code "58") (name "Net-(U5-VREG)") (class "Default")
      (node (ref "C19") (pin "2") (pinfunction "2_2") (pintype "passive"))
      (node (ref "U5") (pin "10") (pinfunction "VREG_10") (pintype "passive"))
    )
    (net (code "59") (name "unconnected-(CN1-Pad3)") (class "Default")
      (node (ref "CN1") (pin "3") (pinfunction "3_3") (pintype "passive+no_connect"))
    )
    (net (code "60") (name "unconnected-(CN1-Pad4)") (class "Default")
      (node (ref "CN1") (pin "4") (pinfunction "4_4") (pintype "passive+no_connect"))
    )
    (net (code "61") (name "unconnected-(CN3-Pad9)") (class "Default")
      (node (ref "CN3") (pin "9") (pinfunction "9_9") (pintype "passive+no_connect"))
    )
    (net (code "62") (name "unconnected-(CN3-Pad10)") (class "Default")
      (node (ref "CN3") (pin "10") (pinfunction "10_10") (pintype "passive+no_connect"))
    )
    (net (code "63") (name "unconnected-(U1-Pad1)") (class "Default")
      (node (ref "U1") (pin "1") (pinfunction "1_1") (pintype "passive+no_connect"))
    )
    (net (code "64") (name "unconnected-(U1-Pad4)") (class "Default")
      (node (ref "U1") (pin "4") (pinfunction "4_4") (pintype "passive+no_connect"))
    )
    (net (code "65") (name "unconnected-(U4-Pad1)") (class "Default")
      (node (ref "U4") (pin "1") (pinfunction "1_1") (pintype "passive+no_connect"))
    )
    (net (code "66") (name "unconnected-(U4-Pad4)") (class "Default")
      (node (ref "U4") (pin "4") (pinfunction "4_4") (pintype "passive+no_connect"))
    )
    (net (code "67") (name "unconnected-(U6-Pad1)") (class "Default")
      (node (ref "U6") (pin "1") (pinfunction "1_1") (pintype "passive+no_connect"))
    )
    (net (code "68") (name "unconnected-(U6-Pad4)") (class "Default")
      (node (ref "U6") (pin "4") (pinfunction "4_4") (pintype "passive+no_connect"))
    )
    (net (code "69") (name "unconnected-(U7-Pad1)") (class "Default")
      (node (ref "U7") (pin "1") (pinfunction "1_1") (pintype "passive+no_connect"))
    )
    (net (code "70") (name "unconnected-(U7-Pad4)") (class "Default")
      (node (ref "U7") (pin "4") (pinfunction "4_4") (pintype "passive+no_connect"))
    )
    (net (code "71") (name "unconnected-(U8-Pad1)") (class "Default")
      (node (ref "U8") (pin "1") (pinfunction "1_1") (pintype "passive+no_connect"))
    )
    (net (code "72") (name "unconnected-(U8-Pad4)") (class "Default")
      (node (ref "U8") (pin "4") (pinfunction "4_4") (pintype "passive+no_connect"))
    )
    (net (code "73") (name "unconnected-(U9-Pad1)") (class "Default")
      (node (ref "U9") (pin "1") (pinfunction "1_1") (pintype "passive+no_connect"))
    )
    (net (code "74") (name "unconnected-(U9-Pad4)") (class "Default")
      (node (ref "U9") (pin "4") (pinfunction "4_4") (pintype "passive+no_connect"))
    )
  )
)
